# SCH_Logix3-Garage-Pad_2024-09-24.net
KiCad netlist of a schematic drawn in EasyEDA
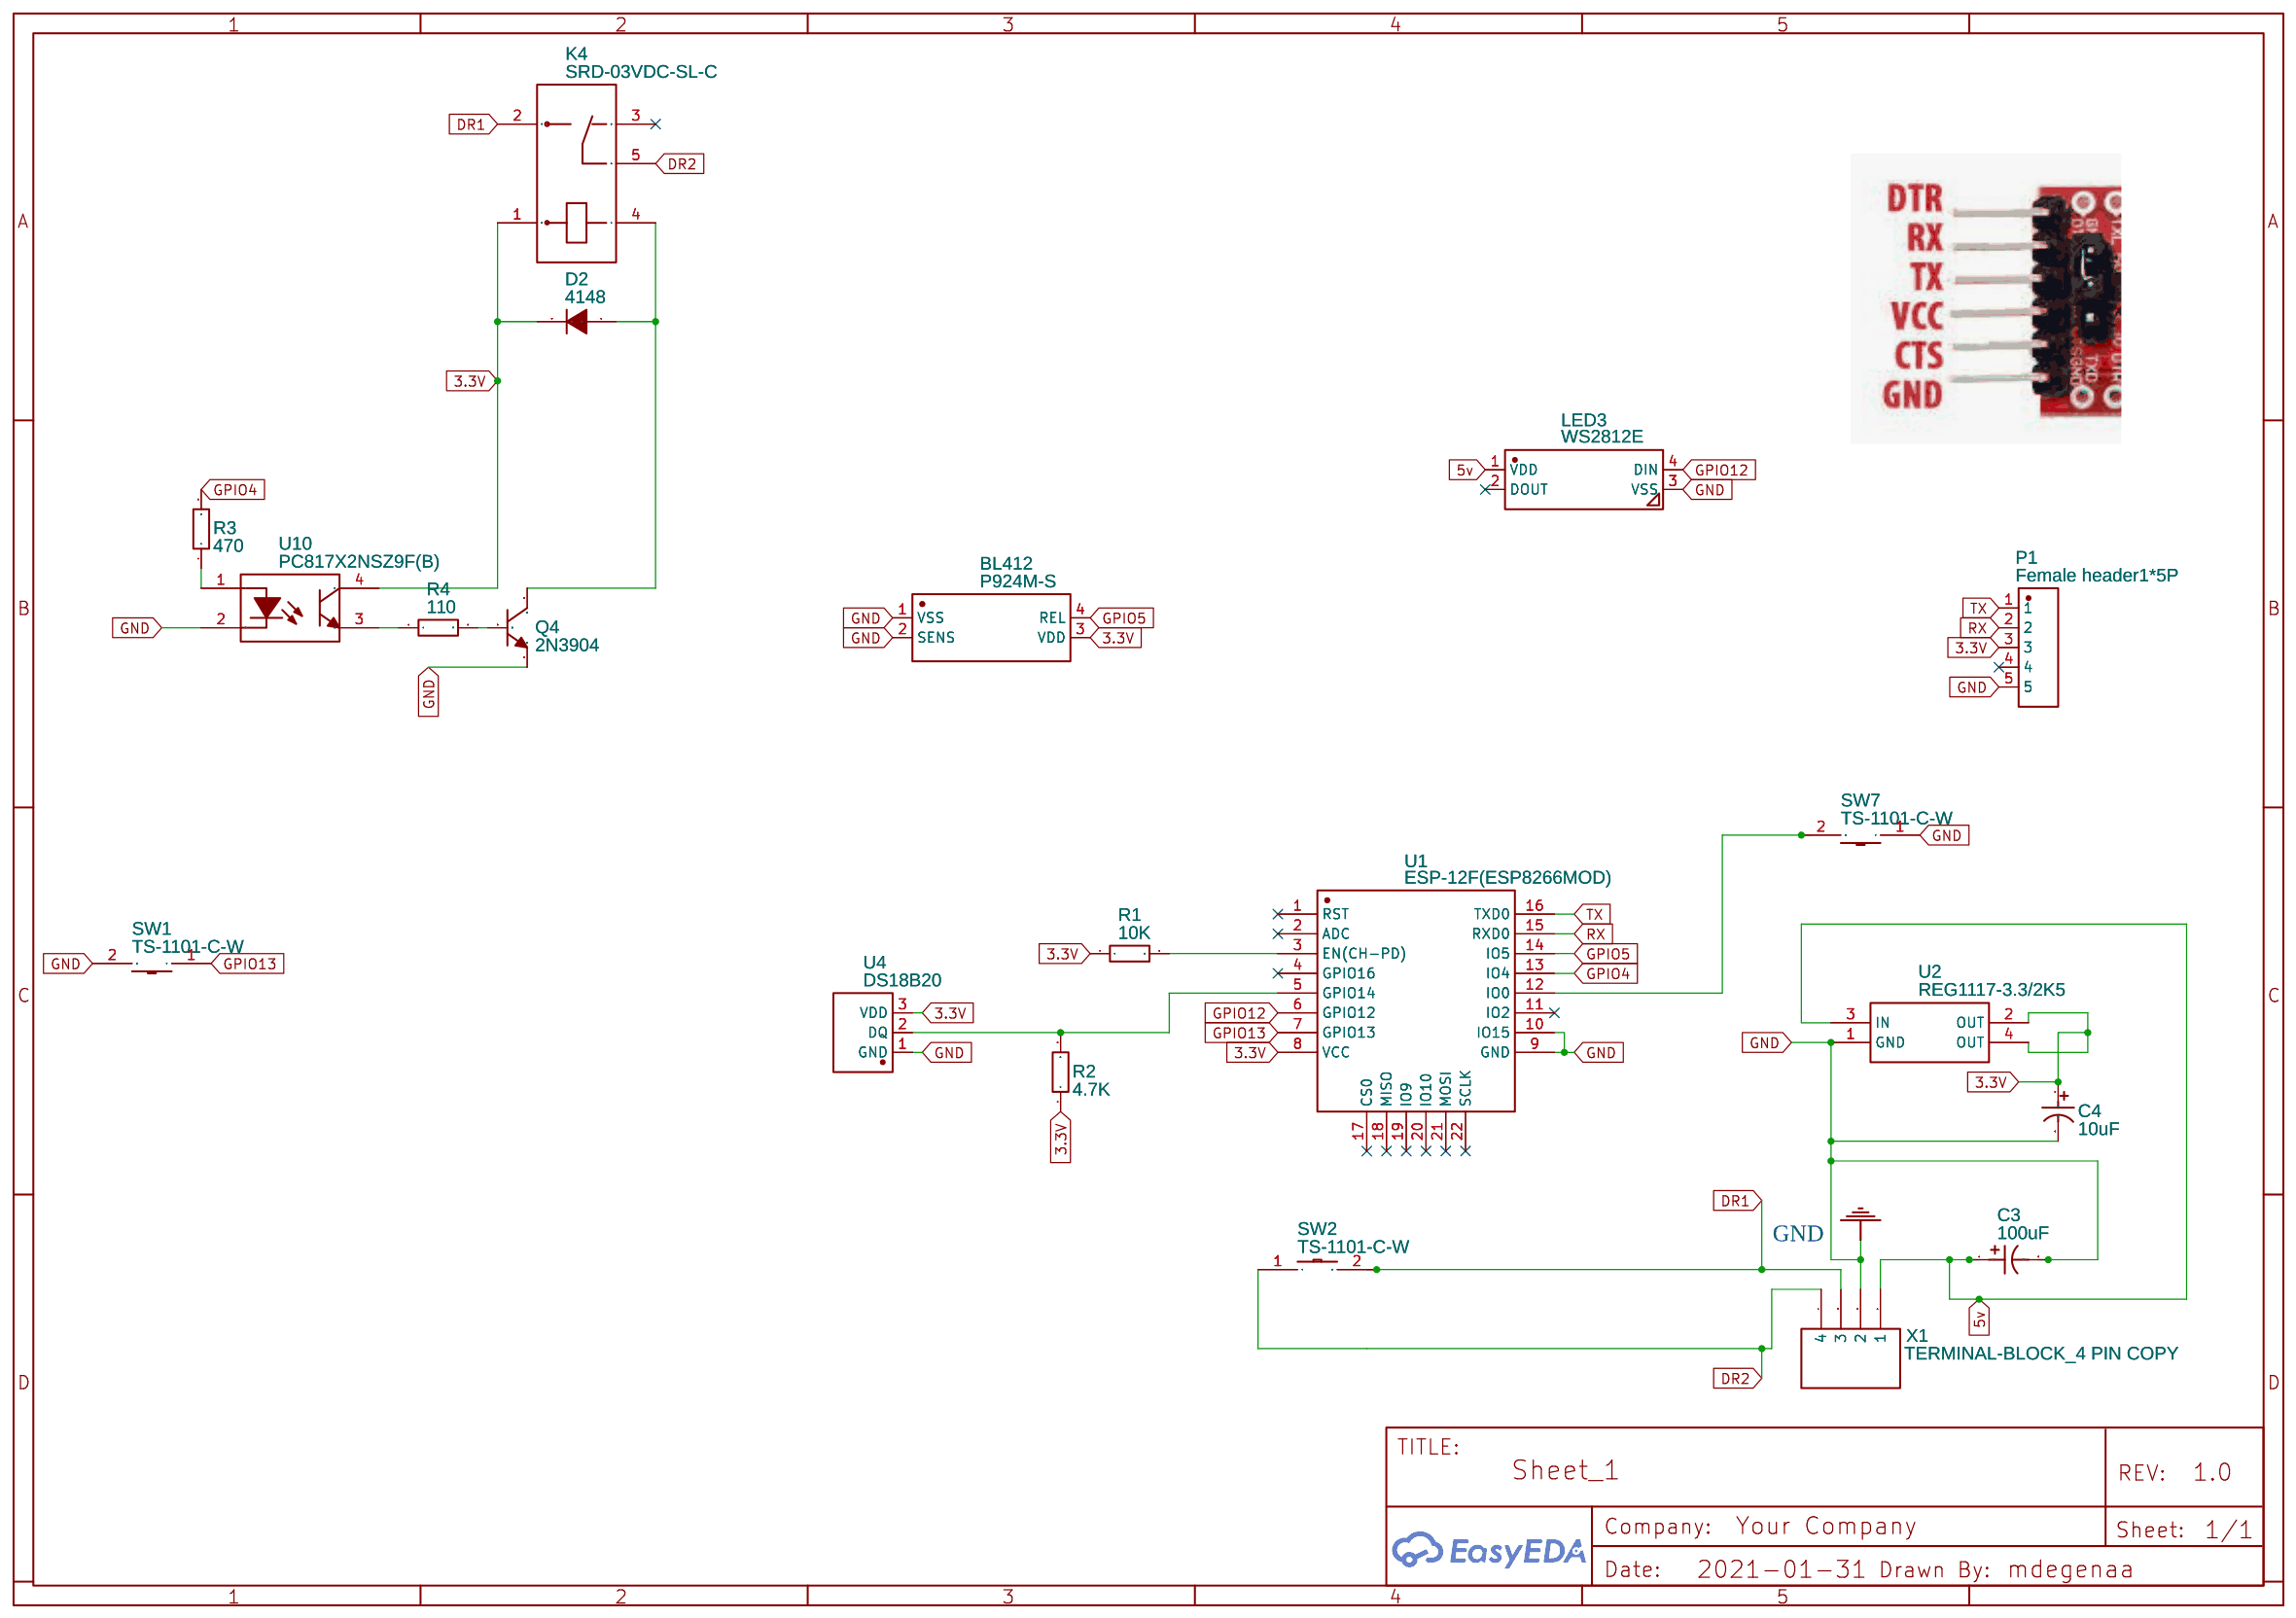
[diagram p0: schematic sheet]

(export (version "E")
  (design (tool "Eeschema 10.0.6"))
  (components
    (comp (ref "BL412")
      (value "P924M-S")
      (fields (field (name "Manufacturer") "Nicera"))
      (libsource (lib "") (part "P924M-S"))
    )
    (comp (ref "C3")
      (value "100uF")
      (fields
        (field (name "Manufacturer Part") "RVT100UF10V67RV0036")
        (field (name "Manufacturer") "KNSCHA(科尼盛)")
      )
      (libsource (lib "") (part "RVT100UF10V67RV0036"))
    )
    (comp (ref "C4")
      (value "10uF")
      (fields (field (name "Manufacturer Part") "RVT1C100M0405") (field (name "Manufacturer") "ROQANG"))
      (libsource (lib "") (part "RVT1C100M0405_C72483"))
    )
    (comp (ref "D2") (value "4148") (libsource (lib "") (part "4148")))
    (comp (ref "K4")
      (value "SRD-03VDC-SL-C")
      (fields (field (name "Manufacturer") "SONGLE"))
      (libsource (lib "") (part "SRD-03VDC-SL-C"))
    )
    (comp (ref "LED3")
      (value "WS2812E")
      (fields (field (name "Manufacturer") "Worldsemi"))
      (libsource (lib "") (part "WS2812E"))
    )
    (comp (ref "P1")
      (value "Female header1*5P")
      (fields (field (name "Manufacturer") "BOOMELE"))
      (libsource (lib "") (part "Female header1*5P"))
    )
    (comp (ref "Q4")
      (value "2N3904")
      (fields (field (name "Manufacturer") "SEMTECH"))
      (libsource (lib "") (part "2N3904"))
    )
    (comp (ref "R1")
      (value "10K")
      (fields (field (name "Manufacturer Part") "RMC120610K5%N") (field (name "Manufacturer") "Tyohm"))
      (libsource (lib "") (part "RMC120610K5%N"))
    )
    (comp (ref "R2")
      (value "4.7K")
      (fields (field (name "Manufacturer Part") "RMC12064.7K5%N") (field (name "Manufacturer") "Tyohm"))
      (libsource (lib "") (part "RMC12064.7K5%N"))
    )
    (comp (ref "R3")
      (value "470")
      (fields
        (field (name "Manufacturer Part") "TC0625B4700T5E")
        (field (name "Manufacturer") "Uniroyal Elec")
      )
      (libsource (lib "") (part "TC0625B4700T5E"))
    )
    (comp (ref "R4")
      (value "110")
      (fields
        (field (name "Manufacturer Part") "AECR1206F110RK9")
        (field (name "Manufacturer") "ResistorToday")
      )
      (libsource (lib "") (part "AECR1206F110RK9"))
    )
    (comp (ref "SW1")
      (value "TS-1101-C-W")
      (fields (field (name "Manufacturer") "XKB Connectivity(中国星坤)"))
      (libsource (lib "") (part "TS-1101-C-W"))
    )
    (comp (ref "SW2")
      (value "TS-1101-C-W")
      (fields (field (name "Manufacturer") "XKB Connectivity(中国星坤)"))
      (libsource (lib "") (part "TS-1101-C-W_1"))
    )
    (comp (ref "SW7")
      (value "TS-1101-C-W")
      (fields (field (name "Manufacturer") "XKB Connectivity(中国星坤)"))
      (libsource (lib "") (part "TS-1101-C-W"))
    )
    (comp (ref "U1")
      (value "ESP-12F(ESP8266MOD)")
      (fields (field (name "Manufacturer") "Ai-Thinker"))
      (libsource (lib "") (part "ESP-12F(ESP8266MOD)"))
    )
    (comp (ref "U2")
      (value "REG1117-3.3/2K5")
      (fields (field (name "Manufacturer") "TI"))
      (libsource (lib "") (part "REG1117-3.3/2K5"))
    )
    (comp (ref "U4")
      (value "DS18B20")
      (fields (field (name "Manufacturer") "Youtai Semiconductor Co., Ltd."))
      (libsource (lib "") (part "DS18B20"))
    )
    (comp (ref "U10")
      (value "PC817X2NSZ9F(B)")
      (fields (field (name "Manufacturer") "SHARP"))
      (libsource (lib "") (part "PC817X2NSZ9F(B)"))
    )
    (comp (ref "X1")
      (value "TERMINAL-BLOCK_4 PIN COPY")
      (libsource (lib "") (part "TERMINAL-BLOCK_4 PIN COPY"))
    )
  )
  (nets
    (net (code "1") (name "3.3V") (class "Default")
      (node (ref "BL412") (pin "3") (pinfunction "VDD_3") (pintype "unspecified"))
      (node (ref "C4") (pin "1") (pinfunction "1_1") (pintype "input"))
      (node (ref "D2") (pin "2") (pinfunction "K_2") (pintype "unspecified"))
      (node (ref "K4") (pin "1") (pinfunction "1_1") (pintype "unspecified"))
      (node (ref "P1") (pin "3") (pinfunction "3_3") (pintype "unspecified"))
      (node (ref "R1") (pin "1") (pinfunction "1_1") (pintype "unspecified"))
      (node (ref "R2") (pin "1") (pinfunction "1_1") (pintype "unspecified"))
      (node (ref "U1") (pin "8") (pinfunction "VCC_8") (pintype "unspecified"))
      (node (ref "U10") (pin "4") (pinfunction "4_4") (pintype "unspecified"))
      (node (ref "U2") (pin "2") (pinfunction "OUT_2") (pintype "passive"))
      (node (ref "U2") (pin "4") (pinfunction "OUT_4") (pintype "passive"))
      (node (ref "U4") (pin "3") (pinfunction "VDD_3") (pintype "unspecified"))
    )
    (net (code "2") (name "5v") (class "Default")
      (node (ref "C3") (pin "1") (pinfunction "1_1") (pintype "input"))
      (node (ref "LED3") (pin "1") (pinfunction "VDD_1") (pintype "unspecified"))
      (node (ref "U2") (pin "3") (pinfunction "IN_3") (pintype "passive"))
      (node (ref "X1") (pin "1") (pinfunction "1_1") (pintype "unspecified"))
    )
    (net (code "3") (name "DR1") (class "Default")
      (node (ref "K4") (pin "2") (pinfunction "2_2") (pintype "unspecified"))
      (node (ref "SW2") (pin "2") (pinfunction "2_2") (pintype "unspecified"))
      (node (ref "X1") (pin "3") (pinfunction "3_3") (pintype "unspecified"))
    )
    (net (code "4") (name "DR2") (class "Default")
      (node (ref "K4") (pin "5") (pinfunction "5_5") (pintype "unspecified"))
      (node (ref "SW2") (pin "1") (pinfunction "1_1") (pintype "unspecified"))
      (node (ref "X1") (pin "4") (pinfunction "4_4") (pintype "unspecified"))
    )
    (net (code "5") (name "GND") (class "Default")
      (node (ref "BL412") (pin "1") (pinfunction "VSS_1") (pintype "unspecified"))
      (node (ref "BL412") (pin "2") (pinfunction "SENS_2") (pintype "unspecified"))
      (node (ref "C3") (pin "2") (pinfunction "2_2") (pintype "input"))
      (node (ref "C4") (pin "2") (pinfunction "2_2") (pintype "input"))
      (node (ref "LED3") (pin "3") (pinfunction "VSS_3") (pintype "unspecified"))
      (node (ref "P1") (pin "5") (pinfunction "5_5") (pintype "unspecified"))
      (node (ref "Q4") (pin "1") (pinfunction "E_1") (pintype "unspecified"))
      (node (ref "SW1") (pin "2") (pinfunction "2_2") (pintype "unspecified"))
      (node (ref "SW7") (pin "1") (pinfunction "1_1") (pintype "unspecified"))
      (node (ref "U1") (pin "10") (pinfunction "IO15_10") (pintype "unspecified"))
      (node (ref "U1") (pin "9") (pinfunction "GND_9") (pintype "unspecified"))
      (node (ref "U10") (pin "2") (pinfunction "2_2") (pintype "unspecified"))
      (node (ref "U2") (pin "1") (pinfunction "GND_1") (pintype "passive"))
      (node (ref "U4") (pin "1") (pinfunction "GND_1") (pintype "unspecified"))
      (node (ref "X1") (pin "2") (pinfunction "2_2") (pintype "unspecified"))
    )
    (net (code "6") (name "GPIO4") (class "Default")
      (node (ref "R3") (pin "2") (pinfunction "2_2") (pintype "unspecified"))
      (node (ref "U1") (pin "13") (pinfunction "IO4_13") (pintype "unspecified"))
    )
    (net (code "7") (name "GPIO5") (class "Default")
      (node (ref "BL412") (pin "4") (pinfunction "REL_4") (pintype "unspecified"))
      (node (ref "U1") (pin "14") (pinfunction "IO5_14") (pintype "unspecified"))
    )
    (net (code "8") (name "GPIO12") (class "Default")
      (node (ref "LED3") (pin "4") (pinfunction "DIN_4") (pintype "unspecified"))
      (node (ref "U1") (pin "6") (pinfunction "GPIO12_6") (pintype "unspecified"))
    )
    (net (code "9") (name "GPIO13") (class "Default")
      (node (ref "SW1") (pin "1") (pinfunction "1_1") (pintype "unspecified"))
      (node (ref "U1") (pin "7") (pinfunction "GPIO13_7") (pintype "unspecified"))
    )
    (net (code "10") (name "Net-(D2-A)") (class "Default")
      (node (ref "D2") (pin "1") (pinfunction "A_1") (pintype "unspecified"))
      (node (ref "K4") (pin "4") (pinfunction "4_4") (pintype "unspecified"))
      (node (ref "Q4") (pin "3") (pinfunction "C_3") (pintype "unspecified"))
    )
    (net (code "11") (name "Net-(Q4-B)") (class "Default")
      (node (ref "Q4") (pin "2") (pinfunction "B_2") (pintype "unspecified"))
      (node (ref "R4") (pin "2") (pinfunction "2_2") (pintype "unspecified"))
    )
    (net (code "12") (name "Net-(R3-Pad1)") (class "Default")
      (node (ref "R3") (pin "1") (pinfunction "1_1") (pintype "unspecified"))
      (node (ref "U10") (pin "1") (pinfunction "1_1") (pintype "unspecified"))
    )
    (net (code "13") (name "Net-(R4-Pad1)") (class "Default")
      (node (ref "R4") (pin "1") (pinfunction "1_1") (pintype "unspecified"))
      (node (ref "U10") (pin "3") (pinfunction "3_3") (pintype "unspecified"))
    )
    (net (code "14") (name "Net-(U1-EN(CH-PD))") (class "Default")
      (node (ref "R1") (pin "2") (pinfunction "2_2") (pintype "unspecified"))
      (node (ref "U1") (pin "3") (pinfunction "EN(CH-PD)_3") (pintype "unspecified"))
    )
    (net (code "15") (name "Net-(U1-GPIO14)") (class "Default")
      (node (ref "R2") (pin "2") (pinfunction "2_2") (pintype "unspecified"))
      (node (ref "U1") (pin "5") (pinfunction "GPIO14_5") (pintype "unspecified"))
      (node (ref "U4") (pin "2") (pinfunction "DQ_2") (pintype "unspecified"))
    )
    (net (code "16") (name "Net-(U1-IO0)") (class "Default")
      (node (ref "SW7") (pin "2") (pinfunction "2_2") (pintype "unspecified"))
      (node (ref "U1") (pin "12") (pinfunction "IO0_12") (pintype "unspecified"))
    )
    (net (code "17") (name "RX") (class "Default")
      (node (ref "P1") (pin "2") (pinfunction "2_2") (pintype "unspecified"))
      (node (ref "U1") (pin "15") (pinfunction "RXD0_15") (pintype "unspecified"))
    )
    (net (code "18") (name "TX") (class "Default")
      (node (ref "P1") (pin "1") (pinfunction "1_1") (pintype "unspecified"))
      (node (ref "U1") (pin "16") (pinfunction "TXD0_16") (pintype "unspecified"))
    )
    (net (code "19") (name "unconnected-(K4-Pad3)") (class "Default")
      (node (ref "K4") (pin "3") (pinfunction "3_3") (pintype "unspecified+no_connect"))
    )
    (net (code "20") (name "unconnected-(LED3-DOUT-Pad2)") (class "Default")
      (node (ref "LED3") (pin "2") (pinfunction "DOUT_2") (pintype "unspecified+no_connect"))
    )
    (net (code "21") (name "unconnected-(P1-Pad4)") (class "Default")
      (node (ref "P1") (pin "4") (pinfunction "4_4") (pintype "unspecified+no_connect"))
    )
    (net (code "22") (name "unconnected-(U1-ADC-Pad2)") (class "Default")
      (node (ref "U1") (pin "2") (pinfunction "ADC_2") (pintype "unspecified+no_connect"))
    )
    (net (code "23") (name "unconnected-(U1-CS0-Pad17)") (class "Default")
      (node (ref "U1") (pin "17") (pinfunction "CS0_17") (pintype "unspecified+no_connect"))
    )
    (net (code "24") (name "unconnected-(U1-GPIO16-Pad4)") (class "Default")
      (node (ref "U1") (pin "4") (pinfunction "GPIO16_4") (pintype "unspecified+no_connect"))
    )
    (net (code "25") (name "unconnected-(U1-IO2-Pad11)") (class "Default")
      (node (ref "U1") (pin "11") (pinfunction "IO2_11") (pintype "unspecified+no_connect"))
    )
    (net (code "26") (name "unconnected-(U1-IO9-Pad19)") (class "Default")
      (node (ref "U1") (pin "19") (pinfunction "IO9_19") (pintype "unspecified+no_connect"))
    )
    (net (code "27") (name "unconnected-(U1-IO10-Pad20)") (class "Default")
      (node (ref "U1") (pin "20") (pinfunction "IO10_20") (pintype "unspecified+no_connect"))
    )
    (net (code "28") (name "unconnected-(U1-MISO-Pad18)") (class "Default")
      (node (ref "U1") (pin "18") (pinfunction "MISO_18") (pintype "unspecified+no_connect"))
    )
    (net (code "29") (name "unconnected-(U1-MOSI-Pad21)") (class "Default")
      (node (ref "U1") (pin "21") (pinfunction "MOSI_21") (pintype "unspecified+no_connect"))
    )
    (net (code "30") (name "unconnected-(U1-RST-Pad1)") (class "Default")
      (node (ref "U1") (pin "1") (pinfunction "RST_1") (pintype "unspecified+no_connect"))
    )
    (net (code "31") (name "unconnected-(U1-SCLK-Pad22)") (class "Default")
      (node (ref "U1") (pin "22") (pinfunction "SCLK_22") (pintype "unspecified+no_connect"))
    )
  )
)
